# SCH_climber-dog_2024-09-03.net
KiCad netlist of a schematic drawn in EasyEDA
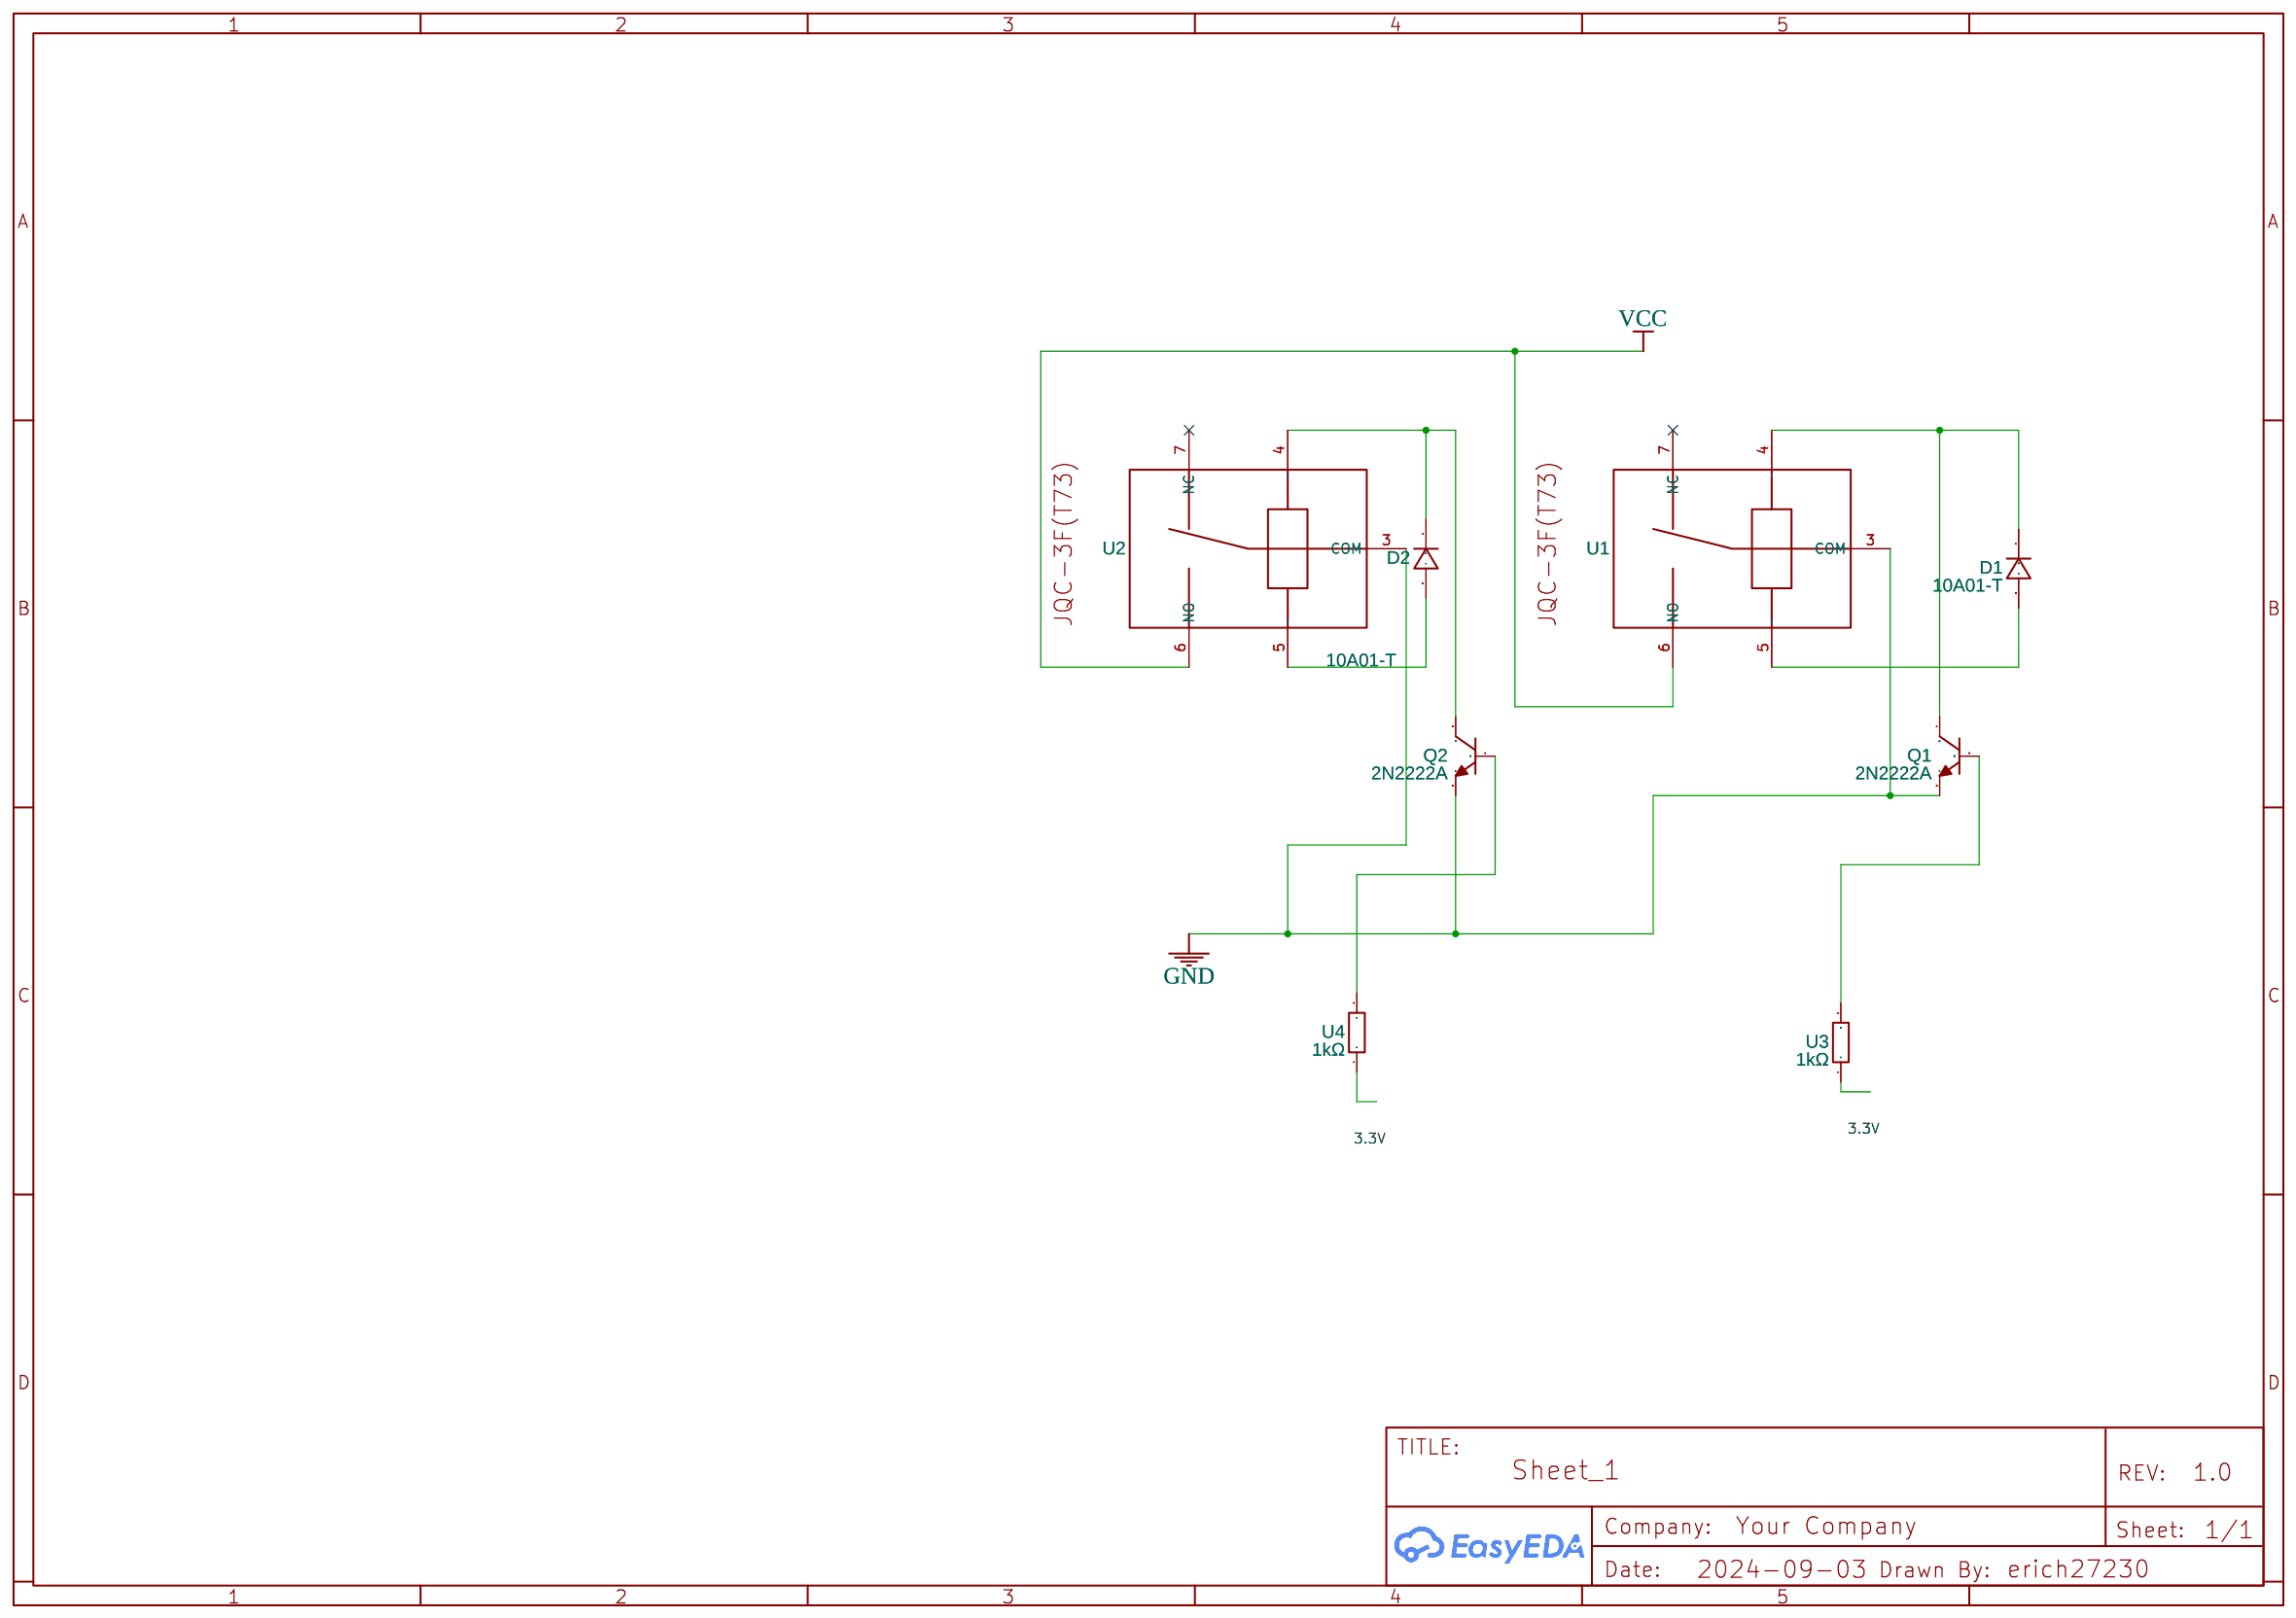
[diagram p0: schematic sheet]

(export (version "E")
  (design (tool "Eeschema 10.0.6"))
  (components
    (comp (ref "D1")
      (value "10A01-T")
      (fields (field (name "Manufacturer") "DIODES(美台)"))
      (libsource (lib "") (part "10A01-T"))
    )
    (comp (ref "D2")
      (value "10A01-T")
      (fields (field (name "Manufacturer") "DIODES(美台)"))
      (libsource (lib "") (part "10A01-T"))
    )
    (comp (ref "Q1")
      (value "2N2222A")
      (fields (field (name "Manufacturer") "BLUE ROCKET(蓝箭)"))
      (libsource (lib "") (part "2N2222A"))
    )
    (comp (ref "Q2")
      (value "2N2222A")
      (fields (field (name "Manufacturer") "BLUE ROCKET(蓝箭)"))
      (libsource (lib "") (part "2N2222A"))
    )
    (comp (ref "U1") (value "JQC-3F(T73) COPY") (libsource (lib "") (part "JQC-3F(T73) COPY")))
    (comp (ref "U2") (value "JQC-3F(T73) COPY") (libsource (lib "") (part "JQC-3F(T73) COPY")))
    (comp (ref "U3")
      (value "1kΩ")
      (fields (field (name "Manufacturer Part") "0402 ±5% 1K") (field (name "Manufacturer") "VO(翔胜)"))
      (libsource (lib "") (part "0402 ±5% 1K"))
    )
    (comp (ref "U4")
      (value "1kΩ")
      (fields (field (name "Manufacturer Part") "0402 ±5% 1K") (field (name "Manufacturer") "VO(翔胜)"))
      (libsource (lib "") (part "0402 ±5% 1K"))
    )
  )
  (nets
    (net (code "2") (name "GND") (class "Default")
      (node (ref "Q1") (pin "3") (pinfunction "E_3") (pintype "unspecified"))
      (node (ref "Q2") (pin "3") (pinfunction "E_3") (pintype "unspecified"))
      (node (ref "U1") (pin "3") (pinfunction "COM_3") (pintype "unspecified"))
      (node (ref "U2") (pin "3") (pinfunction "COM_3") (pintype "unspecified"))
    )
    (net (code "3") (name "Net-(D1-A)") (class "Default")
      (node (ref "D1") (pin "2") (pinfunction "A_2") (pintype "unspecified"))
      (node (ref "U1") (pin "5") (pinfunction "COIL_5") (pintype "unspecified"))
    )
    (net (code "4") (name "Net-(D1-C)") (class "Default")
      (node (ref "D1") (pin "1") (pinfunction "C_1") (pintype "unspecified"))
      (node (ref "Q1") (pin "1") (pinfunction "C_1") (pintype "unspecified"))
      (node (ref "U1") (pin "4") (pinfunction "COIL_4") (pintype "unspecified"))
    )
    (net (code "5") (name "Net-(D2-A)") (class "Default")
      (node (ref "D2") (pin "2") (pinfunction "A_2") (pintype "unspecified"))
      (node (ref "U2") (pin "5") (pinfunction "COIL_5") (pintype "unspecified"))
    )
    (net (code "6") (name "Net-(D2-C)") (class "Default")
      (node (ref "D2") (pin "1") (pinfunction "C_1") (pintype "unspecified"))
      (node (ref "Q2") (pin "1") (pinfunction "C_1") (pintype "unspecified"))
      (node (ref "U2") (pin "4") (pinfunction "COIL_4") (pintype "unspecified"))
    )
    (net (code "7") (name "Net-(Q1-B)") (class "Default")
      (node (ref "Q1") (pin "2") (pinfunction "B_2") (pintype "unspecified"))
      (node (ref "U3") (pin "2") (pinfunction "2_2") (pintype "unspecified"))
    )
    (net (code "8") (name "Net-(Q2-B)") (class "Default")
      (node (ref "Q2") (pin "2") (pinfunction "B_2") (pintype "unspecified"))
      (node (ref "U4") (pin "2") (pinfunction "2_2") (pintype "unspecified"))
    )
    (net (code "9") (name "VCC") (class "Default")
      (node (ref "U1") (pin "6") (pinfunction "NO_6") (pintype "unspecified"))
      (node (ref "U2") (pin "6") (pinfunction "NO_6") (pintype "unspecified"))
    )
    (net (code "10") (name "unconnected-(U1-NC-Pad7)") (class "Default")
      (node (ref "U1") (pin "7") (pinfunction "NC_7") (pintype "unspecified+no_connect"))
    )
    (net (code "11") (name "unconnected-(U2-NC-Pad7)") (class "Default")
      (node (ref "U2") (pin "7") (pinfunction "NC_7") (pintype "unspecified+no_connect"))
    )
    (net (code "12") (name "unconnected-(U3-Pad1)") (class "Default")
      (node (ref "U3") (pin "1") (pinfunction "1_1") (pintype "unspecified"))
    )
    (net (code "13") (name "unconnected-(U4-Pad1)") (class "Default")
      (node (ref "U4") (pin "1") (pinfunction "1_1") (pintype "unspecified"))
    )
  )
)
